# ArduinoZeroV4_0_2.net
KiCad netlist of a schematic drawn in Altium Designer
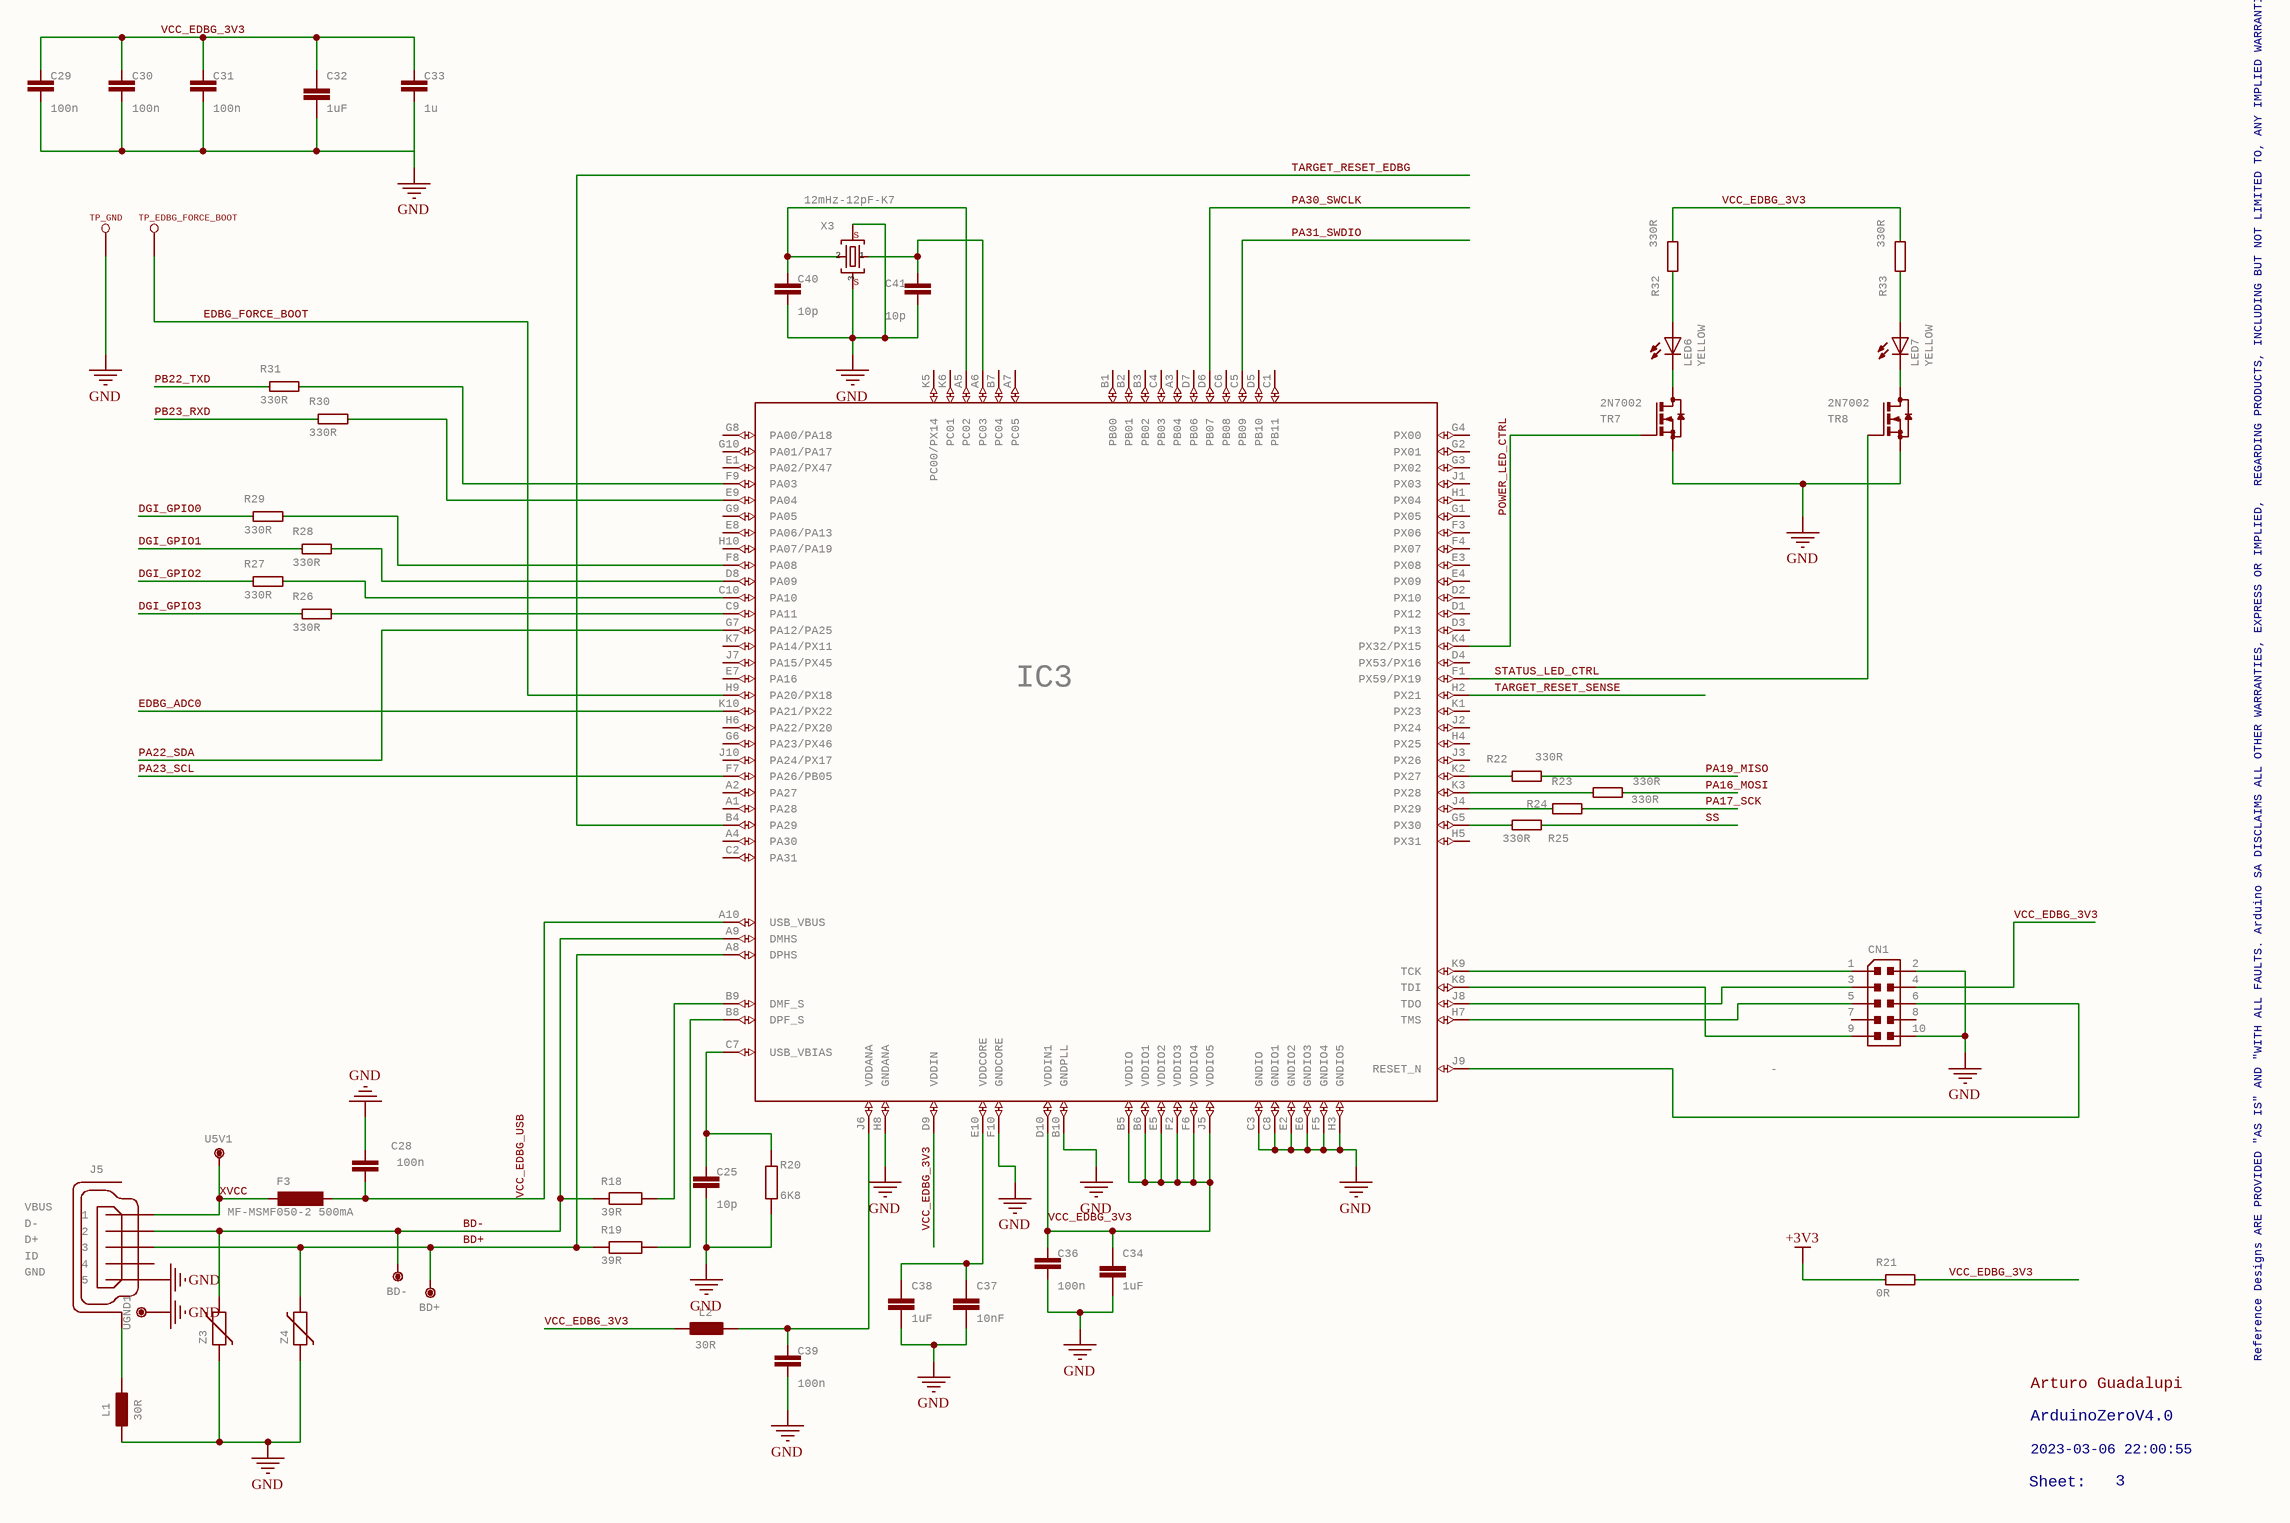
[diagram p0: ArduinoZeroV4.0_2.SchDoc]

(export (version "E")
  (design (tool "Eeschema 10.0.6"))
  (components
    (comp (ref "BD+")
      (value "DNP")
      (footprint "TP-1.00MM")
      (description "Testpoint")
      (libsource (lib "Arduino-utility") (part "TPTP-1.00MM"))
    )
    (comp (ref "BD-")
      (value "DNP")
      (footprint "TP-1.00MM")
      (description "Testpoint")
      (libsource (lib "Arduino-utility") (part "TPTP-1.00MM"))
    )
    (comp (ref "C25")
      (value "10p")
      (footprint "0603-1608X90N")
      (description "SMD Capacitor")
      (libsource (lib "Arduino-rcl") (part "C-0603"))
    )
    (comp (ref "C28")
      (value "100n")
      (footprint "0603-1608X90N")
      (description "SMD Capacitor")
      (fields (field (name "MANUFACTURER") "Murata"))
      (libsource (lib "") (part "C-0603_1"))
    )
    (comp (ref "C29")
      (value "100n")
      (footprint "0603-1608X90N")
      (description "SMD Capacitor")
      (fields (field (name "MANUFACTURER") "Murata"))
      (libsource (lib "Arduino-rcl") (part "C-0603"))
    )
    (comp (ref "C30")
      (value "100n")
      (footprint "0603-1608X90N")
      (description "SMD Capacitor")
      (fields (field (name "MANUFACTURER") "Murata"))
      (libsource (lib "Arduino-rcl") (part "C-0603"))
    )
    (comp (ref "C31")
      (value "100n")
      (footprint "0603-1608X90N")
      (description "SMD Capacitor")
      (fields (field (name "MANUFACTURER") "Murata"))
      (libsource (lib "Arduino-rcl") (part "C-0603"))
    )
    (comp (ref "C32")
      (value "1uF")
      (footprint "C0603-ROUND")
      (description "1uF 0603")
      (fields (field (name "PART_NUMBER") "1uF_0603/GRM188R61E105KA12D"))
      (libsource (lib "Condensatori") (part "0006_1UF_0603/GRM188R61E105KA12D"))
    )
    (comp (ref "C33")
      (value "1u")
      (footprint "0603-1608X90N")
      (description "SMD Capacitor")
      (fields (field (name "MANUFACTURER") "Samsung"))
      (libsource (lib "Arduino-rcl") (part "C-0603"))
    )
    (comp (ref "C34")
      (value "1uF")
      (footprint "C0603-ROUND")
      (description "1uF 0603")
      (fields (field (name "PART_NUMBER") "1uF_0603/GRM188R61E105KA12D"))
      (libsource (lib "Condensatori") (part "0006_1UF_0603/GRM188R61E105KA12D"))
    )
    (comp (ref "C36")
      (value "100n")
      (footprint "0603-1608X90N")
      (description "SMD Capacitor")
      (fields (field (name "MANUFACTURER") "Murata"))
      (libsource (lib "Arduino-rcl") (part "C-0603"))
    )
    (comp (ref "C37")
      (value "10nF")
      (footprint "C0603-ROUND")
      (description "1nF 0603")
      (fields (field (name "PART_NUMBER") "1nF_0603"))
      (libsource (lib "Condensatori") (part "0408_1NF_0603"))
    )
    (comp (ref "C38")
      (value "1uF")
      (footprint "C0603-ROUND")
      (description "1uF 0603")
      (fields (field (name "PART_NUMBER") "1uF_0603/GRM188R61E105KA12D"))
      (libsource (lib "Condensatori") (part "0006_1UF_0603/GRM188R61E105KA12D"))
    )
    (comp (ref "C39")
      (value "100n")
      (footprint "0603-1608X90N")
      (description "SMD Capacitor")
      (fields (field (name "MANUFACTURER") "Murata"))
      (libsource (lib "Arduino-rcl") (part "C-0603"))
    )
    (comp (ref "C40")
      (value "10p")
      (footprint "0603-1608X90N")
      (description "SMD Capacitor")
      (libsource (lib "Arduino-rcl") (part "C-0603"))
    )
    (comp (ref "C41")
      (value "10p")
      (footprint "0603-1608X90N")
      (description "SMD Capacitor")
      (libsource (lib "Arduino-rcl") (part "C-0603"))
    )
    (comp (ref "CN1")
      (value "-")
      (footprint "PINHEAD_2X05_127")
      (description "2x5 PASSO 1,27")
      (libsource (lib "Arduino-connectors") (part "JTAG_CONNECTOR-ROUND"))
    )
    (comp (ref "F3")
      (value "MF-MSMF050-2 500mA")
      (footprint "L1812")
      (description "500 mA Multifuse ï¿½ Polyfuse")
      (fields (field (name "PART_NUMBER") "MF-MSMF050-2"))
      (libsource (lib "Protezione") (part "0002_MF-MSMF050-2"))
    )
    (comp (ref "IC3")
      (value "1791_AT32UC3A4256HHB-C1UR")
      (footprint "VFBGA100")
      (description "ATMEL  32-bit AVR  Microcontroller - VFBGA100")
      (libsource (lib "IntegratedCircuits") (part "1791_AT32UC3A4256HHB-C1UR"))
    )
    (comp (ref "J5")
      (value "-")
      (footprint "ZX62-AB-5PA")
      (description "USB - micro AB USB 2.0 Receptacle Connector 5 Position Surface Mount, Right Angle, Horizontal")
      (fields
        (field (name "VBUS") "VBUS")
        (field (name "D-") "D-")
        (field (name "D+") "D+")
        (field (name "ID") "ID")
        (field (name "GND") "GND")
        (field (name "MANUFACTURER") "Hirose")
      )
      (libsource (lib "Arduino-connectors") (part "USB-MICRO"))
    )
    (comp (ref "L1")
      (value "30R")
      (footprint "0805-R2013X50N")
      (description "SMD ferrite")
      (fields (field (name "MANUFACTURER") "Murata"))
      (libsource (lib "Arduino-rcl") (part "FERRITE0805"))
    )
    (comp (ref "L2")
      (value "30R")
      (footprint "0805-R2013X50N")
      (description "SMD ferrite")
      (fields (field (name "MANUFACTURER") "Murata"))
      (libsource (lib "") (part "FERRITE0805_1"))
    )
    (comp (ref "LED6")
      (value "YELLOW")
      (footprint "CHIPLED_0805")
      (description "LED")
      (fields (field (name "MANUFACTURER") "Lite-On"))
      (libsource (lib "Arduino-diodes") (part "LED-0805"))
    )
    (comp (ref "LED7")
      (value "YELLOW")
      (footprint "CHIPLED_0805")
      (description "LED")
      (fields (field (name "MANUFACTURER") "Lite-On"))
      (libsource (lib "Arduino-diodes") (part "LED-0805"))
    )
    (comp (ref "R18")
      (value "39R")
      (footprint "R0603-ROUND")
      (description "39R 0603")
      (fields (field (name "PART_NUMBER") "39_R_0603") (field (name "LIBRARYNAME") "Resistenze"))
      (libsource (lib "Resistenze") (part "0176_39_R_0603"))
    )
    (comp (ref "R19")
      (value "39R")
      (footprint "R0603-ROUND")
      (description "39R 0603")
      (fields (field (name "PART_NUMBER") "39_R_0603") (field (name "LIBRARYNAME") "Resistenze"))
      (libsource (lib "Resistenze") (part "0176_39_R_0603"))
    )
    (comp (ref "R20")
      (value "6K8")
      (footprint "R0603-ROUND")
      (description "6K8 0603")
      (fields (field (name "PART_NUMBER") "6K8_0603") (field (name "LIBRARYNAME") "Resistenze"))
      (libsource (lib "Resistenze") (part "0164_6K8_0603"))
    )
    (comp (ref "R21")
      (value "0R")
      (footprint "C0603")
      (description "SMD Resistor")
      (fields (field (name "MANUFACTURER") "Yageo"))
      (libsource (lib "Arduino-rcl") (part "R-0603"))
    )
    (comp (ref "R22")
      (value "330R")
      (footprint "C0603")
      (description "SMD Resistor")
      (fields (field (name "MANUFACTURER") "Yageo"))
      (libsource (lib "Arduino-rcl") (part "R-0603"))
    )
    (comp (ref "R23")
      (value "330R")
      (footprint "C0603")
      (description "SMD Resistor")
      (fields (field (name "MANUFACTURER") "Yageo"))
      (libsource (lib "Arduino-rcl") (part "R-0603"))
    )
    (comp (ref "R24")
      (value "330R")
      (footprint "C0603")
      (description "SMD Resistor")
      (fields (field (name "MANUFACTURER") "Yageo"))
      (libsource (lib "Arduino-rcl") (part "R-0603"))
    )
    (comp (ref "R25")
      (value "330R")
      (footprint "C0603")
      (description "SMD Resistor")
      (fields (field (name "MANUFACTURER") "Yageo"))
      (libsource (lib "Arduino-rcl") (part "R-0603"))
    )
    (comp (ref "R26")
      (value "330R")
      (footprint "C0603")
      (description "SMD Resistor")
      (fields (field (name "MANUFACTURER") "Yageo"))
      (libsource (lib "Arduino-rcl") (part "R-0603"))
    )
    (comp (ref "R27")
      (value "330R")
      (footprint "C0603")
      (description "SMD Resistor")
      (fields (field (name "MANUFACTURER") "Yageo"))
      (libsource (lib "Arduino-rcl") (part "R-0603"))
    )
    (comp (ref "R28")
      (value "330R")
      (footprint "C0603")
      (description "SMD Resistor")
      (fields (field (name "MANUFACTURER") "Yageo"))
      (libsource (lib "Arduino-rcl") (part "R-0603"))
    )
    (comp (ref "R29")
      (value "330R")
      (footprint "C0603")
      (description "SMD Resistor")
      (fields (field (name "MANUFACTURER") "Yageo"))
      (libsource (lib "Arduino-rcl") (part "R-0603"))
    )
    (comp (ref "R30")
      (value "330R")
      (footprint "C0603")
      (description "SMD Resistor")
      (fields (field (name "MANUFACTURER") "Yageo"))
      (libsource (lib "Arduino-rcl") (part "R-0603"))
    )
    (comp (ref "R31")
      (value "330R")
      (footprint "C0603")
      (description "SMD Resistor")
      (fields (field (name "MANUFACTURER") "Yageo"))
      (libsource (lib "Arduino-rcl") (part "R-0603"))
    )
    (comp (ref "R32")
      (value "330R")
      (footprint "C0603")
      (description "SMD Resistor")
      (fields (field (name "MANUFACTURER") "Yageo"))
      (libsource (lib "Arduino-rcl") (part "R-0603"))
    )
    (comp (ref "R33")
      (value "330R")
      (footprint "C0603")
      (description "SMD Resistor")
      (fields (field (name "MANUFACTURER") "Yageo"))
      (libsource (lib "Arduino-rcl") (part "R-0603"))
    )
    (comp (ref "TP_EDBG_FORCE_BOOT")
      (value "TP_SP")
      (footprint "TP-SP")
      (libsource (lib "SmartPrj") (part "TP_SP"))
    )
    (comp (ref "TP_GND") (value "TP_SP") (footprint "TP-SP") (libsource (lib "SmartPrj") (part "TP_SP")))
    (comp (ref "TR7")
      (value "2N7002")
      (footprint "SOT23")
      (description "MOSFET N-CH 60V 115MA")
      (fields (field (name "MANUFACTURER") "Micro Commercial Co"))
      (libsource (lib "Arduino-transistors") (part "2N7002T-SOT23"))
    )
    (comp (ref "TR8")
      (value "2N7002")
      (footprint "SOT23")
      (description "MOSFET N-CH 60V 115MA")
      (fields (field (name "MANUFACTURER") "Micro Commercial Co"))
      (libsource (lib "Arduino-transistors") (part "2N7002T-SOT23"))
    )
    (comp (ref "U5V1")
      (value "DNP")
      (footprint "TP-1.00MM")
      (description "Testpoint")
      (libsource (lib "Arduino-utility") (part "TPTP-1.00MM"))
    )
    (comp (ref "UGND1")
      (value "DNP")
      (footprint "TP-1.00MM")
      (description "Testpoint")
      (libsource (lib "Arduino-utility") (part "TPTP-1.00MM"))
    )
    (comp (ref "X3")
      (value "12mHz-12pF-K7")
      (footprint "CRYSTAL-3.2-2.5")
      (description "12Mhz - K7    12pF - SMD")
      (fields
        (field (name "1") "1")
        (field (name "2") "2")
        (field (name "3") "3")
        (field (name "S") "S")
        (field (name "S_1") "S")
        (field (name "LIBRARYNAME") "Cristalli")
      )
      (libsource (lib "Cristalli") (part "0396_12MHZ-12PF-K7"))
    )
    (comp (ref "Z3")
      (value "-")
      (footprint "C0603")
      (description "Varistors")
      (fields (field (name "MANUFACTURER") "Bourns"))
      (libsource (lib "Arduino-rcl") (part "VARISTOR"))
    )
    (comp (ref "Z4")
      (value "-")
      (footprint "C0603")
      (description "Varistors")
      (fields (field (name "MANUFACTURER") "Bourns"))
      (libsource (lib "Arduino-rcl") (part "VARISTOR"))
    )
  )
  (nets
    (net (code "1") (name "+3V3") (class "Default")
      (node (ref "R21") (pin "1") (pinfunction "1_1") (pintype "passive"))
    )
    (net (code "2") (name "/BD+") (class "Default")
      (node (ref "BD+") (pin "X") (pinfunction "P$1_X") (pintype "passive"))
      (node (ref "IC3") (pin "A8") (pinfunction "DPHS_A8") (pintype "bidirectional"))
      (node (ref "J5") (pin "3") (pinfunction "3_3") (pintype "passive"))
      (node (ref "R19") (pin "1") (pinfunction "1_1") (pintype "passive"))
      (node (ref "Z4") (pin "2") (pinfunction "2_2") (pintype "passive"))
    )
    (net (code "3") (name "/BD-") (class "Default")
      (node (ref "BD-") (pin "X") (pinfunction "P$1_X") (pintype "passive"))
      (node (ref "IC3") (pin "A9") (pinfunction "DMHS_A9") (pintype "bidirectional"))
      (node (ref "J5") (pin "2") (pinfunction "2_2") (pintype "passive"))
      (node (ref "R18") (pin "1") (pinfunction "1_1") (pintype "passive"))
      (node (ref "Z3") (pin "2") (pinfunction "2_2") (pintype "passive"))
    )
    (net (code "4") (name "/DGI_GPIO0") (class "Default")
      (node (ref "R29") (pin "1") (pinfunction "1_1") (pintype "passive"))
    )
    (net (code "5") (name "/DGI_GPIO1") (class "Default")
      (node (ref "R28") (pin "1") (pinfunction "1_1") (pintype "passive"))
    )
    (net (code "6") (name "/DGI_GPIO2") (class "Default")
      (node (ref "R27") (pin "1") (pinfunction "1_1") (pintype "passive"))
    )
    (net (code "7") (name "/DGI_GPIO3") (class "Default")
      (node (ref "R26") (pin "1") (pinfunction "1_1") (pintype "passive"))
    )
    (net (code "8") (name "/EDBG_ADC0") (class "Default")
      (node (ref "IC3") (pin "K10") (pinfunction "PA21/PX22_K10") (pintype "bidirectional"))
    )
    (net (code "9") (name "/EDBG_FORCE_BOOT") (class "Default")
      (node (ref "IC3") (pin "H9") (pinfunction "PA20/PX18_H9") (pintype "bidirectional"))
      (node (ref "TP_EDBG_FORCE_BOOT") (pin "X") (pinfunction "TESTP_X") (pintype "passive"))
    )
    (net (code "10") (name "/PA16_MOSI") (class "Default")
      (node (ref "R23") (pin "2") (pinfunction "2_2") (pintype "passive"))
    )
    (net (code "11") (name "/PA17_SCK") (class "Default")
      (node (ref "R24") (pin "2") (pinfunction "2_2") (pintype "passive"))
    )
    (net (code "12") (name "/PA19_MISO") (class "Default")
      (node (ref "R22") (pin "2") (pinfunction "2_2") (pintype "passive"))
    )
    (net (code "13") (name "/PA22_SDA") (class "Default")
      (node (ref "IC3") (pin "G7") (pinfunction "PA12/PA25_G7") (pintype "bidirectional"))
    )
    (net (code "14") (name "/PA23_SCL") (class "Default")
      (node (ref "IC3") (pin "F7") (pinfunction "PA26/PB05_F7") (pintype "bidirectional"))
    )
    (net (code "15") (name "/PA30_SWCLK") (class "Default")
      (node (ref "IC3") (pin "D6") (pinfunction "PB07_D6") (pintype "bidirectional"))
    )
    (net (code "16") (name "/PA31_SWDIO") (class "Default")
      (node (ref "IC3") (pin "C5") (pinfunction "PB09_C5") (pintype "bidirectional"))
    )
    (net (code "17") (name "/PB22_TXD") (class "Default")
      (node (ref "R31") (pin "1") (pinfunction "1_1") (pintype "passive"))
    )
    (net (code "18") (name "/PB23_RXD") (class "Default")
      (node (ref "R30") (pin "1") (pinfunction "1_1") (pintype "passive"))
    )
    (net (code "19") (name "/POWER_LED_CTRL") (class "Default")
      (node (ref "IC3") (pin "K4") (pinfunction "PX32/PX15_K4") (pintype "bidirectional"))
      (node (ref "TR7") (pin "1") (pinfunction "G_1") (pintype "passive"))
    )
    (net (code "20") (name "/SS") (class "Default")
      (node (ref "R25") (pin "2") (pinfunction "2_2") (pintype "passive"))
    )
    (net (code "21") (name "/STATUS_LED_CTRL") (class "Default")
      (node (ref "IC3") (pin "F1") (pinfunction "PX59/PX19_F1") (pintype "bidirectional"))
      (node (ref "TR8") (pin "1") (pinfunction "G_1") (pintype "passive"))
    )
    (net (code "22") (name "/TARGET_RESET_EDBG") (class "Default")
      (node (ref "IC3") (pin "B4") (pinfunction "PA29_B4") (pintype "bidirectional"))
    )
    (net (code "23") (name "/TARGET_RESET_SENSE") (class "Default")
      (node (ref "IC3") (pin "H2") (pinfunction "PX21_H2") (pintype "bidirectional"))
    )
    (net (code "24") (name "/VCC_EDBG_3V3") (class "Default")
      (node (ref "C29") (pin "1") (pinfunction "1_1") (pintype "passive"))
      (node (ref "C30") (pin "1") (pinfunction "1_1") (pintype "passive"))
      (node (ref "C31") (pin "1") (pinfunction "1_1") (pintype "passive"))
      (node (ref "C32") (pin "1") (pinfunction "1_1") (pintype "passive"))
      (node (ref "C33") (pin "1") (pinfunction "1_1") (pintype "passive"))
      (node (ref "C34") (pin "1") (pinfunction "1_1") (pintype "passive"))
      (node (ref "C36") (pin "1") (pinfunction "1_1") (pintype "passive"))
      (node (ref "CN1") (pin "4") (pinfunction "4_4") (pintype "passive"))
      (node (ref "IC3") (pin "B5") (pinfunction "VDDIO_B5") (pintype "bidirectional"))
      (node (ref "IC3") (pin "B6") (pinfunction "VDDIO1_B6") (pintype "bidirectional"))
      (node (ref "IC3") (pin "D10") (pinfunction "VDDIN1_D10") (pintype "bidirectional"))
      (node (ref "IC3") (pin "D9") (pinfunction "VDDIN_D9") (pintype "bidirectional"))
      (node (ref "IC3") (pin "E5") (pinfunction "VDDIO2_E5") (pintype "bidirectional"))
      (node (ref "IC3") (pin "F2") (pinfunction "VDDIO3_F2") (pintype "bidirectional"))
      (node (ref "IC3") (pin "F6") (pinfunction "VDDIO4_F6") (pintype "bidirectional"))
      (node (ref "IC3") (pin "J5") (pinfunction "VDDIO5_J5") (pintype "bidirectional"))
      (node (ref "L2") (pin "1") (pinfunction "1_1") (pintype "passive"))
      (node (ref "R21") (pin "2") (pinfunction "2_2") (pintype "passive"))
      (node (ref "R32") (pin "2") (pinfunction "2_2") (pintype "passive"))
      (node (ref "R33") (pin "2") (pinfunction "2_2") (pintype "passive"))
    )
    (net (code "25") (name "/VCC_EDBG_USB") (class "Default")
      (node (ref "C28") (pin "1") (pinfunction "1_1") (pintype "passive"))
      (node (ref "F3") (pin "1") (pinfunction "1_1") (pintype "passive"))
      (node (ref "IC3") (pin "A10") (pinfunction "USB_VBUS_A10") (pintype "bidirectional"))
    )
    (net (code "26") (name "/XVCC") (class "Default")
      (node (ref "F3") (pin "2") (pinfunction "2_2") (pintype "passive"))
      (node (ref "J5") (pin "1") (pinfunction "1_1") (pintype "passive"))
      (node (ref "U5V1") (pin "X") (pinfunction "P$1_X") (pintype "passive"))
    )
    (net (code "27") (name "GND") (class "Default")
      (node (ref "C25") (pin "2") (pinfunction "2_2") (pintype "passive"))
      (node (ref "C28") (pin "2") (pinfunction "2_2") (pintype "passive"))
      (node (ref "C29") (pin "2") (pinfunction "2_2") (pintype "passive"))
      (node (ref "C30") (pin "2") (pinfunction "2_2") (pintype "passive"))
      (node (ref "C31") (pin "2") (pinfunction "2_2") (pintype "passive"))
      (node (ref "C32") (pin "2") (pinfunction "2_2") (pintype "passive"))
      (node (ref "C33") (pin "2") (pinfunction "2_2") (pintype "passive"))
      (node (ref "C34") (pin "2") (pinfunction "2_2") (pintype "passive"))
      (node (ref "C36") (pin "2") (pinfunction "2_2") (pintype "passive"))
      (node (ref "C37") (pin "2") (pinfunction "2_2") (pintype "passive"))
      (node (ref "C38") (pin "2") (pinfunction "2_2") (pintype "passive"))
      (node (ref "C39") (pin "2") (pinfunction "2_2") (pintype "passive"))
      (node (ref "C40") (pin "2") (pinfunction "2_2") (pintype "passive"))
      (node (ref "C41") (pin "2") (pinfunction "2_2") (pintype "passive"))
      (node (ref "CN1") (pin "10") (pinfunction "10_10") (pintype "passive"))
      (node (ref "CN1") (pin "2") (pinfunction "2_2") (pintype "passive"))
      (node (ref "IC3") (pin "B10") (pinfunction "GNDPLL_B10") (pintype "bidirectional"))
      (node (ref "IC3") (pin "C3") (pinfunction "GNDIO_C3") (pintype "bidirectional"))
      (node (ref "IC3") (pin "C8") (pinfunction "GNDIO1_C8") (pintype "bidirectional"))
      (node (ref "IC3") (pin "E2") (pinfunction "GNDIO2_E2") (pintype "bidirectional"))
      (node (ref "IC3") (pin "E6") (pinfunction "GNDIO3_E6") (pintype "bidirectional"))
      (node (ref "IC3") (pin "F10") (pinfunction "GNDCORE_F10") (pintype "bidirectional"))
      (node (ref "IC3") (pin "F5") (pinfunction "GNDIO4_F5") (pintype "bidirectional"))
      (node (ref "IC3") (pin "H3") (pinfunction "GNDIO5_H3") (pintype "bidirectional"))
      (node (ref "IC3") (pin "H8") (pinfunction "GNDANA_H8") (pintype "bidirectional"))
      (node (ref "J5") (pin "5") (pinfunction "5_5") (pintype "passive"))
      (node (ref "L1") (pin "1") (pinfunction "1_1") (pintype "passive"))
      (node (ref "R20") (pin "1") (pinfunction "1_1") (pintype "passive"))
      (node (ref "TP_GND") (pin "X") (pinfunction "TESTP_X") (pintype "passive"))
      (node (ref "TR7") (pin "2") (pinfunction "S_2") (pintype "passive"))
      (node (ref "TR8") (pin "2") (pinfunction "S_2") (pintype "passive"))
      (node (ref "UGND1") (pin "X") (pinfunction "P$1_X") (pintype "passive"))
      (node (ref "X3") (pin "2") (pinfunction "GND_2") (pintype "passive"))
      (node (ref "X3") (pin "4") (pinfunction "GND_4") (pintype "passive"))
      (node (ref "Z3") (pin "1") (pinfunction "1_1") (pintype "passive"))
      (node (ref "Z4") (pin "1") (pinfunction "1_1") (pintype "passive"))
    )
    (net (code "28") (name "Net-(IC3-DMF_S)") (class "Default")
      (node (ref "IC3") (pin "B9") (pinfunction "DMF_S_B9") (pintype "bidirectional"))
      (node (ref "R18") (pin "2") (pinfunction "2_2") (pintype "passive"))
    )
    (net (code "29") (name "Net-(IC3-DPF_S)") (class "Default")
      (node (ref "IC3") (pin "B8") (pinfunction "DPF_S_B8") (pintype "bidirectional"))
      (node (ref "R19") (pin "2") (pinfunction "2_2") (pintype "passive"))
    )
    (net (code "30") (name "Net-(IC3-PA03)") (class "Default")
      (node (ref "IC3") (pin "F9") (pinfunction "PA03_F9") (pintype "bidirectional"))
      (node (ref "R31") (pin "2") (pinfunction "2_2") (pintype "passive"))
    )
    (net (code "31") (name "Net-(IC3-PA04)") (class "Default")
      (node (ref "IC3") (pin "E9") (pinfunction "PA04_E9") (pintype "bidirectional"))
      (node (ref "R30") (pin "2") (pinfunction "2_2") (pintype "passive"))
    )
    (net (code "32") (name "Net-(IC3-PA08)") (class "Default")
      (node (ref "IC3") (pin "F8") (pinfunction "PA08_F8") (pintype "bidirectional"))
      (node (ref "R29") (pin "2") (pinfunction "2_2") (pintype "passive"))
    )
    (net (code "33") (name "Net-(IC3-PA09)") (class "Default")
      (node (ref "IC3") (pin "D8") (pinfunction "PA09_D8") (pintype "bidirectional"))
      (node (ref "R28") (pin "2") (pinfunction "2_2") (pintype "passive"))
    )
    (net (code "34") (name "Net-(IC3-PA10)") (class "Default")
      (node (ref "IC3") (pin "C10") (pinfunction "PA10_C10") (pintype "bidirectional"))
      (node (ref "R27") (pin "2") (pinfunction "2_2") (pintype "passive"))
    )
    (net (code "35") (name "Net-(IC3-PA11)") (class "Default")
      (node (ref "IC3") (pin "C9") (pinfunction "PA11_C9") (pintype "bidirectional"))
      (node (ref "R26") (pin "2") (pinfunction "2_2") (pintype "passive"))
    )
    (net (code "36") (name "Net-(IC3-PC02)") (class "Default")
      (node (ref "C40") (pin "1") (pinfunction "1_1") (pintype "passive"))
      (node (ref "IC3") (pin "A5") (pinfunction "PC02_A5") (pintype "bidirectional"))
      (node (ref "X3") (pin "3") (pinfunction "C2_3") (pintype "passive"))
    )
    (net (code "37") (name "Net-(IC3-PC03)") (class "Default")
      (node (ref "C41") (pin "1") (pinfunction "1_1") (pintype "passive"))
      (node (ref "IC3") (pin "A6") (pinfunction "PC03_A6") (pintype "bidirectional"))
      (node (ref "X3") (pin "1") (pinfunction "C1_1") (pintype "passive"))
    )
    (net (code "38") (name "Net-(IC3-PX27)") (class "Default")
      (node (ref "IC3") (pin "K2") (pinfunction "PX27_K2") (pintype "bidirectional"))
      (node (ref "R22") (pin "1") (pinfunction "1_1") (pintype "passive"))
    )
    (net (code "39") (name "Net-(IC3-PX28)") (class "Default")
      (node (ref "IC3") (pin "K3") (pinfunction "PX28_K3") (pintype "bidirectional"))
      (node (ref "R23") (pin "1") (pinfunction "1_1") (pintype "passive"))
    )
    (net (code "40") (name "Net-(IC3-PX29)") (class "Default")
      (node (ref "IC3") (pin "J4") (pinfunction "PX29_J4") (pintype "bidirectional"))
      (node (ref "R24") (pin "1") (pinfunction "1_1") (pintype "passive"))
    )
    (net (code "41") (name "Net-(IC3-PX30)") (class "Default")
      (node (ref "IC3") (pin "G5") (pinfunction "PX30_G5") (pintype "bidirectional"))
      (node (ref "R25") (pin "1") (pinfunction "1_1") (pintype "passive"))
    )
    (net (code "42") (name "Net-(IC3-RESET_N)") (class "Default")
      (node (ref "CN1") (pin "6") (pinfunction "6_6") (pintype "passive"))
      (node (ref "IC3") (pin "J9") (pinfunction "RESET_N_J9") (pintype "bidirectional"))
    )
    (net (code "43") (name "Net-(IC3-TCK)") (class "Default")
      (node (ref "CN1") (pin "1") (pinfunction "1_1") (pintype "passive"))
      (node (ref "IC3") (pin "K9") (pinfunction "TCK_K9") (pintype "bidirectional"))
    )
    (net (code "44") (name "Net-(IC3-TDI)") (class "Default")
      (node (ref "CN1") (pin "9") (pinfunction "9_9") (pintype "passive"))
      (node (ref "IC3") (pin "K8") (pinfunction "TDI_K8") (pintype "bidirectional"))
    )
    (net (code "45") (name "Net-(IC3-TDO)") (class "Default")
      (node (ref "CN1") (pin "3") (pinfunction "3_3") (pintype "passive"))
      (node (ref "IC3") (pin "J8") (pinfunction "TDO_J8") (pintype "bidirectional"))
    )
    (net (code "46") (name "Net-(IC3-TMS)") (class "Default")
      (node (ref "CN1") (pin "5") (pinfunction "5_5") (pintype "passive"))
      (node (ref "IC3") (pin "H7") (pinfunction "TMS_H7") (pintype "bidirectional"))
    )
    (net (code "47") (name "Net-(IC3-USB_VBIAS)") (class "Default")
      (node (ref "C25") (pin "1") (pinfunction "1_1") (pintype "passive"))
      (node (ref "IC3") (pin "C7") (pinfunction "USB_VBIAS_C7") (pintype "bidirectional"))
      (node (ref "R20") (pin "2") (pinfunction "2_2") (pintype "passive"))
    )
    (net (code "48") (name "Net-(IC3-VDDANA)") (class "Default")
      (node (ref "C39") (pin "1") (pinfunction "1_1") (pintype "passive"))
      (node (ref "IC3") (pin "J6") (pinfunction "VDDANA_J6") (pintype "bidirectional"))
      (node (ref "L2") (pin "2") (pinfunction "2_2") (pintype "passive"))
    )
    (net (code "49") (name "Net-(IC3-VDDCORE)") (class "Default")
      (node (ref "C37") (pin "1") (pinfunction "1_1") (pintype "passive"))
      (node (ref "C38") (pin "1") (pinfunction "1_1") (pintype "passive"))
      (node (ref "IC3") (pin "E10") (pinfunction "VDDCORE_E10") (pintype "bidirectional"))
    )
    (net (code "50") (name "Net-(J5-SH)") (class "Default")
      (node (ref "J5") (pin "6-11") (pinfunction "SH_6-11") (pintype "passive"))
      (node (ref "L1") (pin "2") (pinfunction "2_2") (pintype "passive"))
    )
    (net (code "51") (name "Net-(LED6-PadA)") (class "Default")
      (node (ref "LED6") (pin "A") (pinfunction "A_A") (pintype "passive"))
      (node (ref "R32") (pin "1") (pinfunction "1_1") (pintype "passive"))
    )
    (net (code "52") (name "Net-(LED7-PadA)") (class "Default")
      (node (ref "LED7") (pin "A") (pinfunction "A_A") (pintype "passive"))
      (node (ref "R33") (pin "1") (pinfunction "1_1") (pintype "passive"))
    )
    (net (code "53") (name "Net-(TR7-D)") (class "Default")
      (node (ref "LED6") (pin "C") (pinfunction "C_C") (pintype "passive"))
      (node (ref "TR7") (pin "3") (pinfunction "D_3") (pintype "passive"))
    )
    (net (code "54") (name "Net-(TR8-D)") (class "Default")
      (node (ref "LED7") (pin "C") (pinfunction "C_C") (pintype "passive"))
      (node (ref "TR8") (pin "3") (pinfunction "D_3") (pintype "passive"))
    )
    (net (code "55") (name "unconnected-(CN1-Pad7)") (class "Default")
      (node (ref "CN1") (pin "7") (pinfunction "7_7") (pintype "passive"))
    )
    (net (code "56") (name "unconnected-(CN1-Pad8)") (class "Default")
      (node (ref "CN1") (pin "8") (pinfunction "8_8") (pintype "passive"))
    )
    (net (code "57") (name "unconnected-(IC3-PA00{slash}PA18-PadG8)") (class "Default")
      (node (ref "IC3") (pin "G8") (pinfunction "PA00/PA18_G8") (pintype "bidirectional"))
    )
    (net (code "58") (name "unconnected-(IC3-PA01{slash}PA17-PadG10)") (class "Default")
      (node (ref "IC3") (pin "G10") (pinfunction "PA01/PA17_G10") (pintype "bidirectional"))
    )
    (net (code "59") (name "unconnected-(IC3-PA02{slash}PX47-PadE1)") (class "Default")
      (node (ref "IC3") (pin "E1") (pinfunction "PA02/PX47_E1") (pintype "bidirectional"))
    )
    (net (code "60") (name "unconnected-(IC3-PA05-PadG9)") (class "Default")
      (node (ref "IC3") (pin "G9") (pinfunction "PA05_G9") (pintype "bidirectional"))
    )
    (net (code "61") (name "unconnected-(IC3-PA06{slash}PA13-PadE8)") (class "Default")
      (node (ref "IC3") (pin "E8") (pinfunction "PA06/PA13_E8") (pintype "bidirectional"))
    )
    (net (code "62") (name "unconnected-(IC3-PA07{slash}PA19-PadH10)") (class "Default")
      (node (ref "IC3") (pin "H10") (pinfunction "PA07/PA19_H10") (pintype "bidirectional"))
    )
    (net (code "63") (name "unconnected-(IC3-PA14{slash}PX11-PadK7)") (class "Default")
      (node (ref "IC3") (pin "K7") (pinfunction "PA14/PX11_K7") (pintype "bidirectional"))
    )
    (net (code "64") (name "unconnected-(IC3-PA15{slash}PX45-PadJ7)") (class "Default")
      (node (ref "IC3") (pin "J7") (pinfunction "PA15/PX45_J7") (pintype "bidirectional"))
    )
    (net (code "65") (name "unconnected-(IC3-PA16-PadE7)") (class "Default")
      (node (ref "IC3") (pin "E7") (pinfunction "PA16_E7") (pintype "bidirectional"))
    )
    (net (code "66") (name "unconnected-(IC3-PA22{slash}PX20-PadH6)") (class "Default")
      (node (ref "IC3") (pin "H6") (pinfunction "PA22/PX20_H6") (pintype "bidirectional"))
    )
    (net (code "67") (name "unconnected-(IC3-PA23{slash}PX46-PadG6)") (class "Default")
      (node (ref "IC3") (pin "G6") (pinfunction "PA23/PX46_G6") (pintype "bidirectional"))
    )
    (net (code "68") (name "unconnected-(IC3-PA24{slash}PX17-PadJ10)") (class "Default")
      (node (ref "IC3") (pin "J10") (pinfunction "PA24/PX17_J10") (pintype "bidirectional"))
    )
    (net (code "69") (name "unconnected-(IC3-PA27-PadA2)") (class "Default")
      (node (ref "IC3") (pin "A2") (pinfunction "PA27_A2") (pintype "bidirectional"))
    )
    (net (code "70") (name "unconnected-(IC3-PA28-PadA1)") (class "Default")
      (node (ref "IC3") (pin "A1") (pinfunction "PA28_A1") (pintype "bidirectional"))
    )
    (net (code "71") (name "unconnected-(IC3-PA30-PadA4)") (class "Default")
      (node (ref "IC3") (pin "A4") (pinfunction "PA30_A4") (pintype "bidirectional"))
    )
    (net (code "72") (name "unconnected-(IC3-PA31-PadC2)") (class "Default")
      (node (ref "IC3") (pin "C2") (pinfunction "PA31_C2") (pintype "bidirectional"))
    )
    (net (code "73") (name "unconnected-(IC3-PB00-PadB1)") (class "Default")
      (node (ref "IC3") (pin "B1") (pinfunction "PB00_B1") (pintype "bidirectional"))
    )
    (net (code "74") (name "unconnected-(IC3-PB01-PadB2)") (class "Default")
      (node (ref "IC3") (pin "B2") (pinfunction "PB01_B2") (pintype "bidirectional"))
    )
    (net (code "75") (name "unconnected-(IC3-PB02-PadB3)") (class "Default")
      (node (ref "IC3") (pin "B3") (pinfunction "PB02_B3") (pintype "bidirectional"))
    )
    (net (code "76") (name "unconnected-(IC3-PB03-PadC4)") (class "Default")
      (node (ref "IC3") (pin "C4") (pinfunction "PB03_C4") (pintype "bidirectional"))
    )
    (net (code "77") (name "unconnected-(IC3-PB04-PadA3)") (class "Default")
      (node (ref "IC3") (pin "A3") (pinfunction "PB04_A3") (pintype "bidirectional"))
    )
    (net (code "78") (name "unconnected-(IC3-PB06-PadD7)") (class "Default")
      (node (ref "IC3") (pin "D7") (pinfunction "PB06_D7") (pintype "bidirectional"))
    )
    (net (code "79") (name "unconnected-(IC3-PB08-PadC6)") (class "Default")
      (node (ref "IC3") (pin "C6") (pinfunction "PB08_C6") (pintype "bidirectional"))
    )
    (net (code "80") (name "unconnected-(IC3-PB10-PadD5)") (class "Default")
      (node (ref "IC3") (pin "D5") (pinfunction "PB10_D5") (pintype "bidirectional"))
    )
    (net (code "81") (name "unconnected-(IC3-PB11-PadC1)") (class "Default")
      (node (ref "IC3") (pin "C1") (pinfunction "PB11_C1") (pintype "bidirectional"))
    )
    (net (code "82") (name "unconnected-(IC3-PC00{slash}PX14-PadK5)") (class "Default")
      (node (ref "IC3") (pin "K5") (pinfunction "PC00/PX14_K5") (pintype "bidirectional"))
    )
    (net (code "83") (name "unconnected-(IC3-PC01-PadK6)") (class "Default")
      (node (ref "IC3") (pin "K6") (pinfunction "PC01_K6") (pintype "bidirectional"))
    )
    (net (code "84") (name "unconnected-(IC3-PC04-PadB7)") (class "Default")
      (node (ref "IC3") (pin "B7") (pinfunction "PC04_B7") (pintype "bidirectional"))
    )
    (net (code "85") (name "unconnected-(IC3-PC05-PadA7)") (class "Default")
      (node (ref "IC3") (pin "A7") (pinfunction "PC05_A7") (pintype "bidirectional"))
    )
    (net (code "86") (name "unconnected-(IC3-PX00-PadG4)") (class "Default")
      (node (ref "IC3") (pin "G4") (pinfunction "PX00_G4") (pintype "bidirectional"))
    )
    (net (code "87") (name "unconnected-(IC3-PX01-PadG2)") (class "Default")
      (node (ref "IC3") (pin "G2") (pinfunction "PX01_G2") (pintype "bidirectional"))
    )
    (net (code "88") (name "unconnected-(IC3-PX02-PadG3)") (class "Default")
      (node (ref "IC3") (pin "G3") (pinfunction "PX02_G3") (pintype "bidirectional"))
    )
    (net (code "89") (name "unconnected-(IC3-PX03-PadJ1)") (class "Default")
      (node (ref "IC3") (pin "J1") (pinfunction "PX03_J1") (pintype "bidirectional"))
    )
    (net (code "90") (name "unconnected-(IC3-PX04-PadH1)") (class "Default")
      (node (ref "IC3") (pin "H1") (pinfunction "PX04_H1") (pintype "bidirectional"))
    )
    (net (code "91") (name "unconnected-(IC3-PX05-PadG1)") (class "Default")
      (node (ref "IC3") (pin "G1") (pinfunction "PX05_G1") (pintype "bidirectional"))
    )
    (net (code "92") (name "unconnected-(IC3-PX06-PadF3)") (class "Default")
      (node (ref "IC3") (pin "F3") (pinfunction "PX06_F3") (pintype "bidirectional"))
    )
    (net (code "93") (name "unconnected-(IC3-PX07-PadF4)") (class "Default")
      (node (ref "IC3") (pin "F4") (pinfunction "PX07_F4") (pintype "bidirectional"))
    )
    (net (code "94") (name "unconnected-(IC3-PX08-PadE3)") (class "Default")
      (node (ref "IC3") (pin "E3") (pinfunction "PX08_E3") (pintype "bidirectional"))
    )
    (net (code "95") (name "unconnected-(IC3-PX09-PadE4)") (class "Default")
      (node (ref "IC3") (pin "E4") (pinfunction "PX09_E4") (pintype "bidirectional"))
    )
    (net (code "96") (name "unconnected-(IC3-PX10-PadD2)") (class "Default")
      (node (ref "IC3") (pin "D2") (pinfunction "PX10_D2") (pintype "bidirectional"))
    )
    (net (code "97") (name "unconnected-(IC3-PX12-PadD1)") (class "Default")
      (node (ref "IC3") (pin "D1") (pinfunction "PX12_D1") (pintype "bidirectional"))
    )
    (net (code "98") (name "unconnected-(IC3-PX13-PadD3)") (class "Default")
      (node (ref "IC3") (pin "D3") (pinfunction "PX13_D3") (pintype "bidirectional"))
    )
    (net (code "99") (name "unconnected-(IC3-PX23-PadK1)") (class "Default")
      (node (ref "IC3") (pin "K1") (pinfunction "PX23_K1") (pintype "bidirectional"))
    )
    (net (code "100") (name "unconnected-(IC3-PX24-PadJ2)") (class "Default")
      (node (ref "IC3") (pin "J2") (pinfunction "PX24_J2") (pintype "bidirectional"))
    )
    (net (code "101") (name "unconnected-(IC3-PX25-PadH4)") (class "Default")
      (node (ref "IC3") (pin "H4") (pinfunction "PX25_H4") (pintype "bidirectional"))
    )
    (net (code "102") (name "unconnected-(IC3-PX26-PadJ3)") (class "Default")
      (node (ref "IC3") (pin "J3") (pinfunction "PX26_J3") (pintype "bidirectional"))
    )
    (net (code "103") (name "unconnected-(IC3-PX31-PadH5)") (class "Default")
      (node (ref "IC3") (pin "H5") (pinfunction "PX31_H5") (pintype "bidirectional"))
    )
    (net (code "104") (name "unconnected-(IC3-PX53{slash}PX16-PadD4)") (class "Default")
      (node (ref "IC3") (pin "D4") (pinfunction "PX53/PX16_D4") (pintype "bidirectional"))
    )
    (net (code "105") (name "unconnected-(J5-Pad4)") (class "Default")
      (node (ref "J5") (pin "4") (pinfunction "4_4") (pintype "passive"))
    )
  )
)
